# auto_shield_final.net
KiCad netlist of a schematic drawn in EAGLE
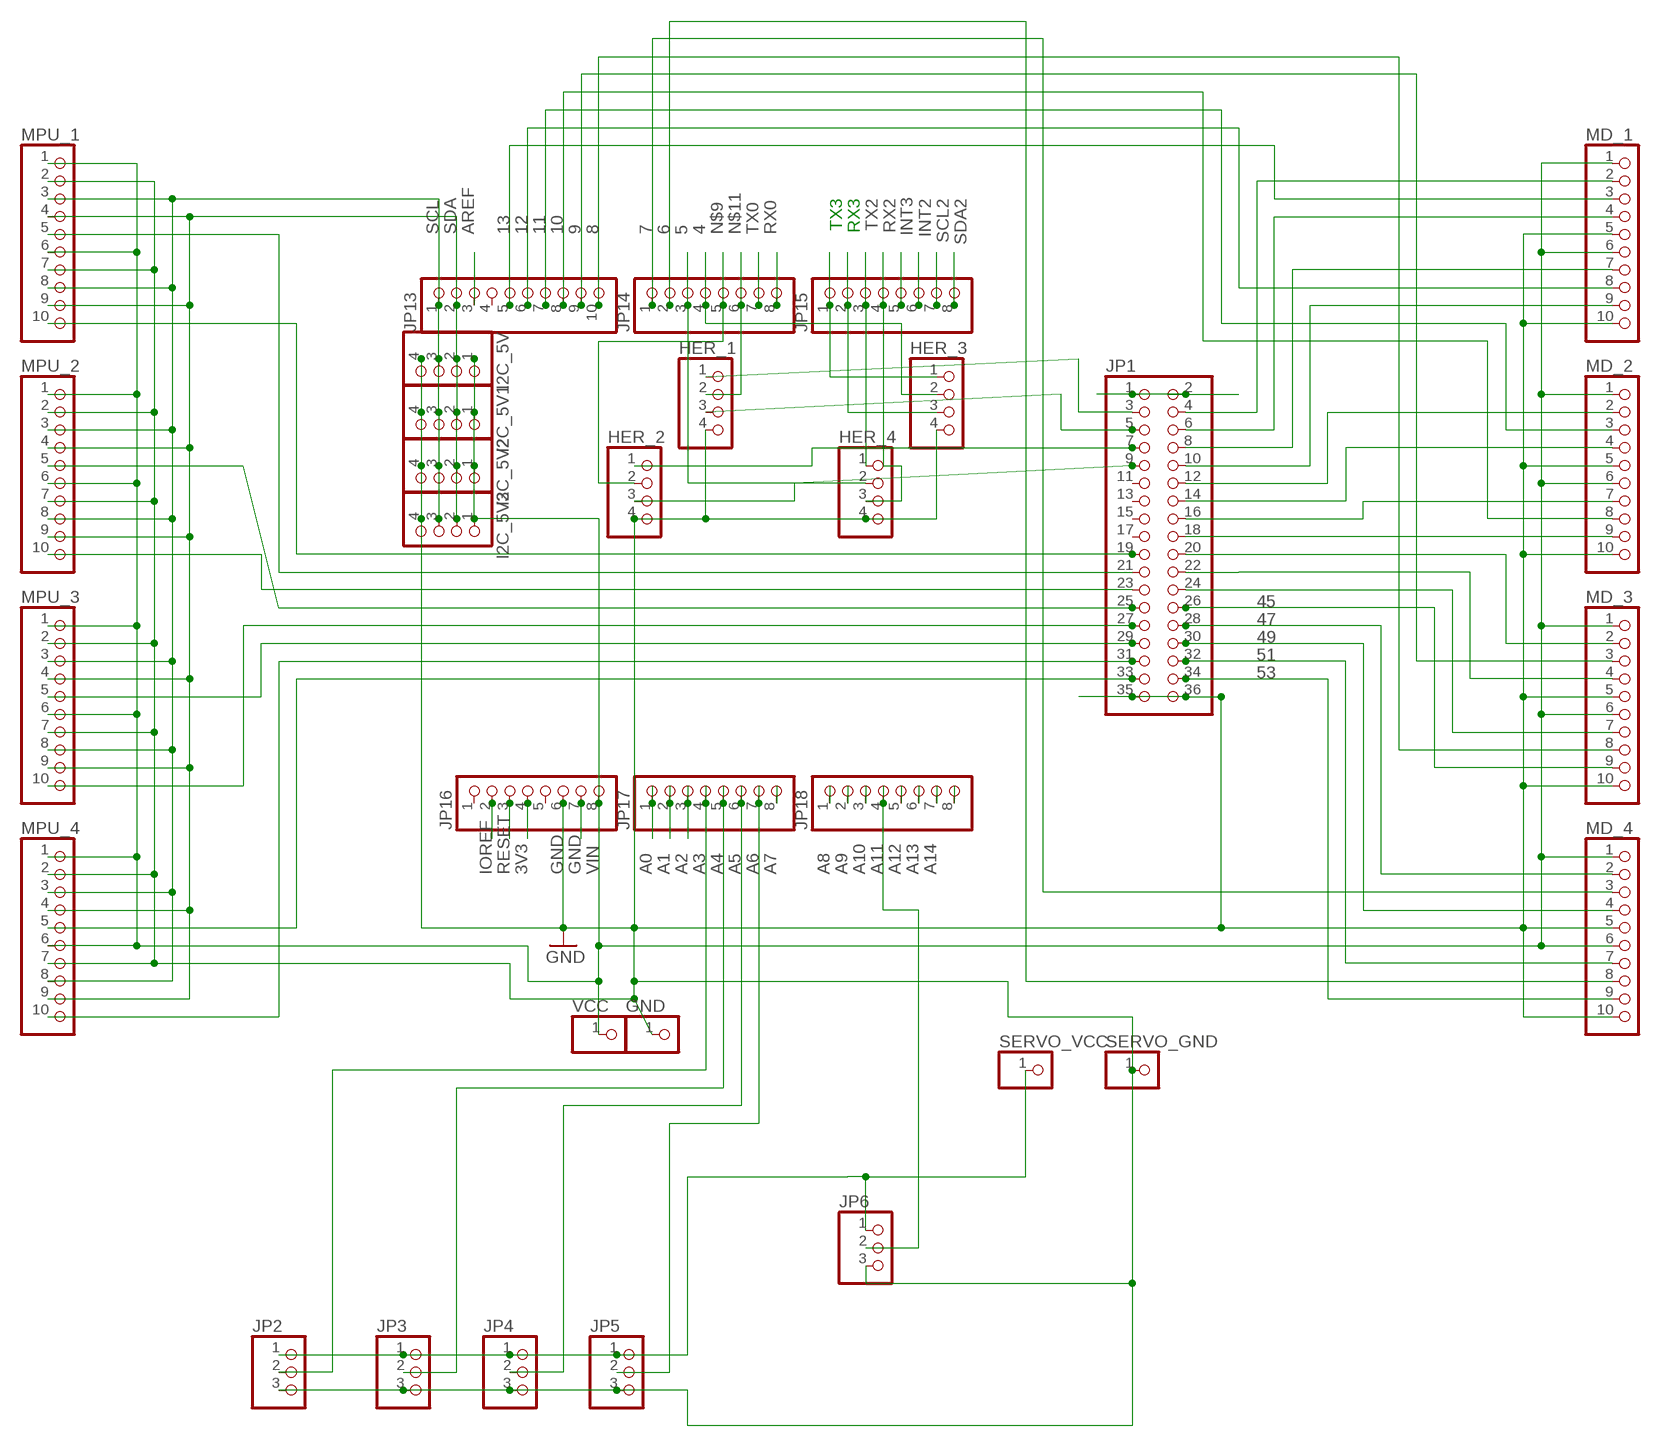
[diagram p0: schematic, sheet 1]

(export (version "E")
  (design (tool "Eeschema 10.0.6"))
  (components
    (comp (ref "GND")
      (value "PINHD-1X1")
      (footprint "eagle-import:1X01")
      (libsource (lib "eagle-import") (part "PINHD-1X1"))
    )
    (comp (ref "HER_1")
      (value "PINHD-1X4")
      (footprint "eagle-import:1X04")
      (libsource (lib "eagle-import") (part "PINHD-1X4"))
    )
    (comp (ref "HER_2")
      (value "PINHD-1X4")
      (footprint "eagle-import:1X04")
      (libsource (lib "eagle-import") (part "PINHD-1X4"))
    )
    (comp (ref "HER_3")
      (value "PINHD-1X4")
      (footprint "eagle-import:1X04")
      (libsource (lib "eagle-import") (part "PINHD-1X4"))
    )
    (comp (ref "HER_4")
      (value "PINHD-1X4")
      (footprint "eagle-import:1X04")
      (libsource (lib "eagle-import") (part "PINHD-1X4"))
    )
    (comp (ref "I2C_5V")
      (value "PINHD-1X4")
      (footprint "eagle-import:1X04")
      (libsource (lib "eagle-import") (part "PINHD-1X4"))
    )
    (comp (ref "I2C_5V1")
      (value "PINHD-1X4")
      (footprint "eagle-import:1X04")
      (libsource (lib "eagle-import") (part "PINHD-1X4"))
    )
    (comp (ref "I2C_5V2")
      (value "PINHD-1X4")
      (footprint "eagle-import:1X04")
      (libsource (lib "eagle-import") (part "PINHD-1X4"))
    )
    (comp (ref "I2C_5V3")
      (value "PINHD-1X4")
      (footprint "eagle-import:1X04")
      (libsource (lib "eagle-import") (part "PINHD-1X4"))
    )
    (comp (ref "JP1")
      (value "PINHD-2X18")
      (footprint "eagle-import:2X18")
      (libsource (lib "eagle-import") (part "PINHD-2X18"))
    )
    (comp (ref "JP2")
      (value "PINHD-1X3")
      (footprint "eagle-import:1X03")
      (libsource (lib "eagle-import") (part "PINHD-1X3"))
    )
    (comp (ref "JP3")
      (value "PINHD-1X3")
      (footprint "eagle-import:1X03")
      (libsource (lib "eagle-import") (part "PINHD-1X3"))
    )
    (comp (ref "JP4")
      (value "PINHD-1X3")
      (footprint "eagle-import:1X03")
      (libsource (lib "eagle-import") (part "PINHD-1X3"))
    )
    (comp (ref "JP5")
      (value "PINHD-1X3")
      (footprint "eagle-import:1X03")
      (libsource (lib "eagle-import") (part "PINHD-1X3"))
    )
    (comp (ref "JP6")
      (value "PINHD-1X3")
      (footprint "eagle-import:1X03")
      (libsource (lib "eagle-import") (part "PINHD-1X3"))
    )
    (comp (ref "JP13")
      (value "PINHD-1X10")
      (footprint "eagle-import:1X10")
      (libsource (lib "eagle-import") (part "PINHD-1X10"))
    )
    (comp (ref "JP14")
      (value "PINHD-1X8")
      (footprint "eagle-import:1X08")
      (libsource (lib "eagle-import") (part "PINHD-1X8"))
    )
    (comp (ref "JP15")
      (value "PINHD-1X8")
      (footprint "eagle-import:1X08")
      (libsource (lib "eagle-import") (part "PINHD-1X8"))
    )
    (comp (ref "JP16")
      (value "PINHD-1X8")
      (footprint "eagle-import:1X08")
      (libsource (lib "eagle-import") (part "PINHD-1X8"))
    )
    (comp (ref "JP17")
      (value "PINHD-1X8")
      (footprint "eagle-import:1X08")
      (libsource (lib "eagle-import") (part "PINHD-1X8"))
    )
    (comp (ref "JP18")
      (value "PINHD-1X8")
      (footprint "eagle-import:1X08")
      (libsource (lib "eagle-import") (part "PINHD-1X8"))
    )
    (comp (ref "MD_1")
      (value "PINHD-1X10")
      (footprint "eagle-import:1X10")
      (libsource (lib "eagle-import") (part "pinhead_325_PINHD-1X10"))
    )
    (comp (ref "MD_2")
      (value "PINHD-1X10")
      (footprint "eagle-import:1X10")
      (libsource (lib "eagle-import") (part "pinhead_325_PINHD-1X10"))
    )
    (comp (ref "MD_3")
      (value "PINHD-1X10")
      (footprint "eagle-import:1X10")
      (libsource (lib "eagle-import") (part "pinhead_325_PINHD-1X10"))
    )
    (comp (ref "MD_4")
      (value "PINHD-1X10")
      (footprint "eagle-import:1X10")
      (libsource (lib "eagle-import") (part "pinhead_325_PINHD-1X10"))
    )
    (comp (ref "MPU_1")
      (value "PINHD-1X10")
      (footprint "eagle-import:1X10")
      (libsource (lib "eagle-import") (part "pinhead_325_PINHD-1X10"))
    )
    (comp (ref "MPU_2")
      (value "PINHD-1X10")
      (footprint "eagle-import:1X10")
      (libsource (lib "eagle-import") (part "pinhead_325_PINHD-1X10"))
    )
    (comp (ref "MPU_3")
      (value "PINHD-1X10")
      (footprint "eagle-import:1X10")
      (libsource (lib "eagle-import") (part "pinhead_325_PINHD-1X10"))
    )
    (comp (ref "MPU_4")
      (value "PINHD-1X10")
      (footprint "eagle-import:1X10")
      (libsource (lib "eagle-import") (part "pinhead_325_PINHD-1X10"))
    )
    (comp (ref "SERVO_GND")
      (value "PINHD-1X1")
      (footprint "eagle-import:1X01")
      (libsource (lib "eagle-import") (part "PINHD-1X1"))
    )
    (comp (ref "SERVO_VCC")
      (value "PINHD-1X1")
      (footprint "eagle-import:1X01")
      (libsource (lib "eagle-import") (part "PINHD-1X1"))
    )
    (comp (ref "VCC")
      (value "PINHD-1X1")
      (footprint "eagle-import:1X01")
      (libsource (lib "eagle-import") (part "PINHD-1X1"))
    )
  )
  (nets
    (net (code "1") (name "/3V3") (class "Default")
      (node (ref "JP16") (pin "4") (pinfunction "4_4") (pintype "passive"))
    )
    (net (code "2") (name "/4") (class "Default")
      (node (ref "HER_3") (pin "2") (pinfunction "2_2") (pintype "passive"))
      (node (ref "JP14") (pin "4") (pinfunction "4_4") (pintype "passive"))
    )
    (net (code "3") (name "/5") (class "Default")
      (node (ref "HER_4") (pin "2") (pinfunction "2_2") (pintype "passive"))
      (node (ref "JP14") (pin "3") (pinfunction "3_3") (pintype "passive"))
    )
    (net (code "4") (name "/6") (class "Default")
      (node (ref "JP14") (pin "2") (pinfunction "2_2") (pintype "passive"))
      (node (ref "MD_4") (pin "8") (pinfunction "8_8") (pintype "passive"))
    )
    (net (code "5") (name "/7") (class "Default")
      (node (ref "JP14") (pin "1") (pinfunction "1_1") (pintype "passive"))
      (node (ref "MD_4") (pin "3") (pinfunction "3_3") (pintype "passive"))
    )
    (net (code "6") (name "/8") (class "Default")
      (node (ref "JP13") (pin "10") (pinfunction "10_10") (pintype "passive"))
      (node (ref "MD_3") (pin "8") (pinfunction "8_8") (pintype "passive"))
    )
    (net (code "7") (name "/9") (class "Default")
      (node (ref "JP13") (pin "9") (pinfunction "9_9") (pintype "passive"))
      (node (ref "MD_3") (pin "3") (pinfunction "3_3") (pintype "passive"))
    )
    (net (code "8") (name "/10") (class "Default")
      (node (ref "JP13") (pin "8") (pinfunction "8_8") (pintype "passive"))
      (node (ref "MD_2") (pin "8") (pinfunction "8_8") (pintype "passive"))
    )
    (net (code "9") (name "/11") (class "Default")
      (node (ref "JP13") (pin "7") (pinfunction "7_7") (pintype "passive"))
      (node (ref "MD_2") (pin "3") (pinfunction "3_3") (pintype "passive"))
    )
    (net (code "10") (name "/12") (class "Default")
      (node (ref "JP13") (pin "6") (pinfunction "6_6") (pintype "passive"))
      (node (ref "MD_1") (pin "8") (pinfunction "8_8") (pintype "passive"))
    )
    (net (code "11") (name "/13") (class "Default")
      (node (ref "JP13") (pin "5") (pinfunction "5_5") (pintype "passive"))
      (node (ref "MD_1") (pin "3") (pinfunction "3_3") (pintype "passive"))
    )
    (net (code "12") (name "/45") (class "Default")
      (node (ref "JP1") (pin "26") (pinfunction "26_26") (pintype "passive"))
      (node (ref "MD_3") (pin "9") (pinfunction "9_9") (pintype "passive"))
    )
    (net (code "13") (name "/47") (class "Default")
      (node (ref "JP1") (pin "28") (pinfunction "28_28") (pintype "passive"))
      (node (ref "MD_4") (pin "2") (pinfunction "2_2") (pintype "passive"))
    )
    (net (code "14") (name "/49") (class "Default")
      (node (ref "JP1") (pin "30") (pinfunction "30_30") (pintype "passive"))
      (node (ref "MD_4") (pin "4") (pinfunction "4_4") (pintype "passive"))
    )
    (net (code "15") (name "/51") (class "Default")
      (node (ref "JP1") (pin "32") (pinfunction "32_32") (pintype "passive"))
      (node (ref "MD_4") (pin "7") (pinfunction "7_7") (pintype "passive"))
    )
    (net (code "16") (name "/53") (class "Default")
      (node (ref "JP1") (pin "34") (pinfunction "34_34") (pintype "passive"))
      (node (ref "MD_4") (pin "9") (pinfunction "9_9") (pintype "passive"))
    )
    (net (code "17") (name "/A0") (class "Default")
      (node (ref "JP17") (pin "1") (pinfunction "1_1") (pintype "passive"))
    )
    (net (code "18") (name "/A1") (class "Default")
      (node (ref "JP17") (pin "2") (pinfunction "2_2") (pintype "passive"))
    )
    (net (code "19") (name "/A2") (class "Default")
      (node (ref "JP17") (pin "3") (pinfunction "3_3") (pintype "passive"))
    )
    (net (code "20") (name "/A3") (class "Default")
      (node (ref "JP17") (pin "4") (pinfunction "4_4") (pintype "passive"))
      (node (ref "JP2") (pin "2") (pinfunction "2_2") (pintype "passive"))
    )
    (net (code "21") (name "/A4") (class "Default")
      (node (ref "JP17") (pin "5") (pinfunction "5_5") (pintype "passive"))
      (node (ref "JP3") (pin "2") (pinfunction "2_2") (pintype "passive"))
    )
    (net (code "22") (name "/A5") (class "Default")
      (node (ref "JP17") (pin "6") (pinfunction "6_6") (pintype "passive"))
      (node (ref "JP4") (pin "2") (pinfunction "2_2") (pintype "passive"))
    )
    (net (code "23") (name "/A6") (class "Default")
      (node (ref "JP17") (pin "7") (pinfunction "7_7") (pintype "passive"))
      (node (ref "JP5") (pin "2") (pinfunction "2_2") (pintype "passive"))
    )
    (net (code "24") (name "/A7") (class "Default")
      (node (ref "JP17") (pin "8") (pinfunction "8_8") (pintype "passive"))
    )
    (net (code "25") (name "/A8") (class "Default")
      (node (ref "JP18") (pin "1") (pinfunction "1_1") (pintype "passive"))
    )
    (net (code "26") (name "/A9") (class "Default")
      (node (ref "JP18") (pin "2") (pinfunction "2_2") (pintype "passive"))
    )
    (net (code "27") (name "/A10") (class "Default")
      (node (ref "JP18") (pin "3") (pinfunction "3_3") (pintype "passive"))
    )
    (net (code "28") (name "/A11") (class "Default")
      (node (ref "JP18") (pin "4") (pinfunction "4_4") (pintype "passive"))
      (node (ref "JP6") (pin "2") (pinfunction "2_2") (pintype "passive"))
    )
    (net (code "29") (name "/A12") (class "Default")
      (node (ref "JP18") (pin "5") (pinfunction "5_5") (pintype "passive"))
    )
    (net (code "30") (name "/A13") (class "Default")
      (node (ref "JP18") (pin "6") (pinfunction "6_6") (pintype "passive"))
    )
    (net (code "31") (name "/A14") (class "Default")
      (node (ref "JP18") (pin "7") (pinfunction "7_7") (pintype "passive"))
    )
    (net (code "32") (name "/AREF") (class "Default")
      (node (ref "JP13") (pin "3") (pinfunction "3_3") (pintype "passive"))
    )
    (net (code "33") (name "/INT2") (class "Default")
      (node (ref "JP15") (pin "6") (pinfunction "6_6") (pintype "passive"))
    )
    (net (code "34") (name "/INT3") (class "Default")
      (node (ref "JP15") (pin "5") (pinfunction "5_5") (pintype "passive"))
    )
    (net (code "35") (name "/IOREF") (class "Default")
      (node (ref "JP16") (pin "2") (pinfunction "2_2") (pintype "passive"))
    )
    (net (code "36") (name "/N$9") (class "Default")
      (node (ref "HER_2") (pin "2") (pinfunction "2_2") (pintype "passive"))
      (node (ref "JP14") (pin "5") (pinfunction "5_5") (pintype "passive"))
    )
    (net (code "37") (name "/N$11") (class "Default")
      (node (ref "HER_1") (pin "2") (pinfunction "2_2") (pintype "passive"))
      (node (ref "JP14") (pin "6") (pinfunction "6_6") (pintype "passive"))
    )
    (net (code "38") (name "/RESET") (class "Default")
      (node (ref "JP16") (pin "3") (pinfunction "3_3") (pintype "passive"))
    )
    (net (code "39") (name "/RX0") (class "Default")
      (node (ref "JP14") (pin "8") (pinfunction "8_8") (pintype "passive"))
    )
    (net (code "40") (name "/RX2") (class "Default")
      (node (ref "HER_4") (pin "3") (pinfunction "3_3") (pintype "passive"))
      (node (ref "JP15") (pin "4") (pinfunction "4_4") (pintype "passive"))
    )
    (net (code "41") (name "/RX3") (class "Default")
      (node (ref "HER_3") (pin "3") (pinfunction "3_3") (pintype "passive"))
      (node (ref "JP15") (pin "2") (pinfunction "2_2") (pintype "passive"))
    )
    (net (code "42") (name "/SCL") (class "Default")
      (node (ref "I2C_5V") (pin "3") (pinfunction "3_3") (pintype "passive"))
      (node (ref "I2C_5V1") (pin "3") (pinfunction "3_3") (pintype "passive"))
      (node (ref "I2C_5V2") (pin "3") (pinfunction "3_3") (pintype "passive"))
      (node (ref "I2C_5V3") (pin "3") (pinfunction "3_3") (pintype "passive"))
      (node (ref "JP13") (pin "1") (pinfunction "1_1") (pintype "passive"))
      (node (ref "MPU_1") (pin "3") (pinfunction "3_3") (pintype "passive"))
      (node (ref "MPU_1") (pin "8") (pinfunction "8_8") (pintype "passive"))
      (node (ref "MPU_2") (pin "3") (pinfunction "3_3") (pintype "passive"))
      (node (ref "MPU_2") (pin "8") (pinfunction "8_8") (pintype "passive"))
      (node (ref "MPU_3") (pin "3") (pinfunction "3_3") (pintype "passive"))
      (node (ref "MPU_3") (pin "8") (pinfunction "8_8") (pintype "passive"))
      (node (ref "MPU_4") (pin "3") (pinfunction "3_3") (pintype "passive"))
      (node (ref "MPU_4") (pin "8") (pinfunction "8_8") (pintype "passive"))
    )
    (net (code "43") (name "/SCL2") (class "Default")
      (node (ref "JP15") (pin "7") (pinfunction "7_7") (pintype "passive"))
    )
    (net (code "44") (name "/SDA") (class "Default")
      (node (ref "I2C_5V") (pin "2") (pinfunction "2_2") (pintype "passive"))
      (node (ref "I2C_5V1") (pin "2") (pinfunction "2_2") (pintype "passive"))
      (node (ref "I2C_5V2") (pin "2") (pinfunction "2_2") (pintype "passive"))
      (node (ref "I2C_5V3") (pin "2") (pinfunction "2_2") (pintype "passive"))
      (node (ref "JP13") (pin "2") (pinfunction "2_2") (pintype "passive"))
      (node (ref "MPU_1") (pin "4") (pinfunction "4_4") (pintype "passive"))
      (node (ref "MPU_1") (pin "9") (pinfunction "9_9") (pintype "passive"))
      (node (ref "MPU_2") (pin "4") (pinfunction "4_4") (pintype "passive"))
      (node (ref "MPU_2") (pin "9") (pinfunction "9_9") (pintype "passive"))
      (node (ref "MPU_3") (pin "4") (pinfunction "4_4") (pintype "passive"))
      (node (ref "MPU_3") (pin "9") (pinfunction "9_9") (pintype "passive"))
      (node (ref "MPU_4") (pin "4") (pinfunction "4_4") (pintype "passive"))
      (node (ref "MPU_4") (pin "9") (pinfunction "9_9") (pintype "passive"))
    )
    (net (code "45") (name "/SDA2") (class "Default")
      (node (ref "JP15") (pin "8") (pinfunction "8_8") (pintype "passive"))
    )
    (net (code "46") (name "/TX0") (class "Default")
      (node (ref "JP14") (pin "7") (pinfunction "7_7") (pintype "passive"))
    )
    (net (code "47") (name "/TX2") (class "Default")
      (node (ref "HER_4") (pin "1") (pinfunction "1_1") (pintype "passive"))
      (node (ref "JP15") (pin "3") (pinfunction "3_3") (pintype "passive"))
    )
    (net (code "48") (name "/TX3") (class "Default")
      (node (ref "HER_3") (pin "1") (pinfunction "1_1") (pintype "passive"))
      (node (ref "JP15") (pin "1") (pinfunction "1_1") (pintype "passive"))
    )
    (net (code "49") (name "/VIN") (class "Default")
      (node (ref "I2C_5V") (pin "1") (pinfunction "1_1") (pintype "passive"))
      (node (ref "I2C_5V1") (pin "1") (pinfunction "1_1") (pintype "passive"))
      (node (ref "I2C_5V2") (pin "1") (pinfunction "1_1") (pintype "passive"))
      (node (ref "I2C_5V3") (pin "1") (pinfunction "1_1") (pintype "passive"))
      (node (ref "JP16") (pin "8") (pinfunction "8_8") (pintype "passive"))
      (node (ref "MD_1") (pin "1") (pinfunction "1_1") (pintype "passive"))
      (node (ref "MD_1") (pin "6") (pinfunction "6_6") (pintype "passive"))
      (node (ref "MD_2") (pin "1") (pinfunction "1_1") (pintype "passive"))
      (node (ref "MD_2") (pin "6") (pinfunction "6_6") (pintype "passive"))
      (node (ref "MD_3") (pin "1") (pinfunction "1_1") (pintype "passive"))
      (node (ref "MD_3") (pin "6") (pinfunction "6_6") (pintype "passive"))
      (node (ref "MD_4") (pin "1") (pinfunction "1_1") (pintype "passive"))
      (node (ref "MD_4") (pin "6") (pinfunction "6_6") (pintype "passive"))
      (node (ref "MPU_1") (pin "1") (pinfunction "1_1") (pintype "passive"))
      (node (ref "MPU_1") (pin "6") (pinfunction "6_6") (pintype "passive"))
      (node (ref "MPU_2") (pin "1") (pinfunction "1_1") (pintype "passive"))
      (node (ref "MPU_2") (pin "6") (pinfunction "6_6") (pintype "passive"))
      (node (ref "MPU_3") (pin "1") (pinfunction "1_1") (pintype "passive"))
      (node (ref "MPU_3") (pin "6") (pinfunction "6_6") (pintype "passive"))
      (node (ref "MPU_4") (pin "1") (pinfunction "1_1") (pintype "passive"))
      (node (ref "MPU_4") (pin "6") (pinfunction "6_6") (pintype "passive"))
      (node (ref "VCC") (pin "1") (pinfunction "1_1") (pintype "passive"))
    )
    (net (code "50") (name "GND") (class "Default")
      (node (ref "GND") (pin "1") (pinfunction "1_1") (pintype "passive"))
      (node (ref "HER_1") (pin "4") (pinfunction "4_4") (pintype "passive"))
      (node (ref "HER_2") (pin "4") (pinfunction "4_4") (pintype "passive"))
      (node (ref "HER_3") (pin "4") (pinfunction "4_4") (pintype "passive"))
      (node (ref "HER_4") (pin "4") (pinfunction "4_4") (pintype "passive"))
      (node (ref "I2C_5V") (pin "4") (pinfunction "4_4") (pintype "passive"))
      (node (ref "I2C_5V1") (pin "4") (pinfunction "4_4") (pintype "passive"))
      (node (ref "I2C_5V2") (pin "4") (pinfunction "4_4") (pintype "passive"))
      (node (ref "I2C_5V3") (pin "4") (pinfunction "4_4") (pintype "passive"))
      (node (ref "JP1") (pin "35") (pinfunction "35_35") (pintype "passive"))
      (node (ref "JP1") (pin "36") (pinfunction "36_36") (pintype "passive"))
      (node (ref "JP16") (pin "6") (pinfunction "6_6") (pintype "passive"))
      (node (ref "JP16") (pin "7") (pinfunction "7_7") (pintype "passive"))
      (node (ref "JP2") (pin "3") (pinfunction "3_3") (pintype "passive"))
      (node (ref "JP3") (pin "3") (pinfunction "3_3") (pintype "passive"))
      (node (ref "JP4") (pin "3") (pinfunction "3_3") (pintype "passive"))
      (node (ref "JP5") (pin "3") (pinfunction "3_3") (pintype "passive"))
      (node (ref "JP6") (pin "3") (pinfunction "3_3") (pintype "passive"))
      (node (ref "MD_1") (pin "10") (pinfunction "10_10") (pintype "passive"))
      (node (ref "MD_1") (pin "5") (pinfunction "5_5") (pintype "passive"))
      (node (ref "MD_2") (pin "10") (pinfunction "10_10") (pintype "passive"))
      (node (ref "MD_2") (pin "5") (pinfunction "5_5") (pintype "passive"))
      (node (ref "MD_3") (pin "10") (pinfunction "10_10") (pintype "passive"))
      (node (ref "MD_3") (pin "5") (pinfunction "5_5") (pintype "passive"))
      (node (ref "MD_4") (pin "10") (pinfunction "10_10") (pintype "passive"))
      (node (ref "MD_4") (pin "5") (pinfunction "5_5") (pintype "passive"))
      (node (ref "MPU_1") (pin "2") (pinfunction "2_2") (pintype "passive"))
      (node (ref "MPU_1") (pin "7") (pinfunction "7_7") (pintype "passive"))
      (node (ref "MPU_2") (pin "2") (pinfunction "2_2") (pintype "passive"))
      (node (ref "MPU_2") (pin "7") (pinfunction "7_7") (pintype "passive"))
      (node (ref "MPU_3") (pin "2") (pinfunction "2_2") (pintype "passive"))
      (node (ref "MPU_3") (pin "7") (pinfunction "7_7") (pintype "passive"))
      (node (ref "MPU_4") (pin "2") (pinfunction "2_2") (pintype "passive"))
      (node (ref "MPU_4") (pin "7") (pinfunction "7_7") (pintype "passive"))
      (node (ref "SERVO_GND") (pin "1") (pinfunction "1_1") (pintype "passive"))
    )
    (net (code "51") (name "Net-(HER_1-Pad1)") (class "Default")
      (node (ref "HER_1") (pin "1") (pinfunction "1_1") (pintype "passive"))
      (node (ref "JP1") (pin "3") (pinfunction "3_3") (pintype "passive"))
    )
    (net (code "52") (name "Net-(HER_1-Pad3)") (class "Default")
      (node (ref "HER_1") (pin "3") (pinfunction "3_3") (pintype "passive"))
      (node (ref "JP1") (pin "5") (pinfunction "5_5") (pintype "passive"))
    )
    (net (code "53") (name "Net-(HER_2-Pad1)") (class "Default")
      (node (ref "HER_2") (pin "1") (pinfunction "1_1") (pintype "passive"))
      (node (ref "JP1") (pin "7") (pinfunction "7_7") (pintype "passive"))
    )
    (net (code "54") (name "Net-(HER_2-Pad3)") (class "Default")
      (node (ref "HER_2") (pin "3") (pinfunction "3_3") (pintype "passive"))
      (node (ref "JP1") (pin "9") (pinfunction "9_9") (pintype "passive"))
    )
    (net (code "55") (name "Net-(JP1-Pad1)") (class "Default")
      (node (ref "JP1") (pin "1") (pinfunction "1_1") (pintype "passive"))
      (node (ref "JP1") (pin "2") (pinfunction "2_2") (pintype "passive"))
    )
    (net (code "56") (name "Net-(JP1-Pad4)") (class "Default")
      (node (ref "JP1") (pin "4") (pinfunction "4_4") (pintype "passive"))
      (node (ref "MD_1") (pin "2") (pinfunction "2_2") (pintype "passive"))
    )
    (net (code "57") (name "Net-(JP1-Pad6)") (class "Default")
      (node (ref "JP1") (pin "6") (pinfunction "6_6") (pintype "passive"))
      (node (ref "MD_1") (pin "4") (pinfunction "4_4") (pintype "passive"))
    )
    (net (code "58") (name "Net-(JP1-Pad8)") (class "Default")
      (node (ref "JP1") (pin "8") (pinfunction "8_8") (pintype "passive"))
      (node (ref "MD_1") (pin "7") (pinfunction "7_7") (pintype "passive"))
    )
    (net (code "59") (name "Net-(JP1-Pad10)") (class "Default")
      (node (ref "JP1") (pin "10") (pinfunction "10_10") (pintype "passive"))
      (node (ref "MD_1") (pin "9") (pinfunction "9_9") (pintype "passive"))
    )
    (net (code "60") (name "Net-(JP1-Pad12)") (class "Default")
      (node (ref "JP1") (pin "12") (pinfunction "12_12") (pintype "passive"))
      (node (ref "MD_2") (pin "2") (pinfunction "2_2") (pintype "passive"))
    )
    (net (code "61") (name "Net-(JP1-Pad14)") (class "Default")
      (node (ref "JP1") (pin "14") (pinfunction "14_14") (pintype "passive"))
      (node (ref "MD_2") (pin "4") (pinfunction "4_4") (pintype "passive"))
    )
    (net (code "62") (name "Net-(JP1-Pad16)") (class "Default")
      (node (ref "JP1") (pin "16") (pinfunction "16_16") (pintype "passive"))
      (node (ref "MD_2") (pin "7") (pinfunction "7_7") (pintype "passive"))
    )
    (net (code "63") (name "Net-(JP1-Pad18)") (class "Default")
      (node (ref "JP1") (pin "18") (pinfunction "18_18") (pintype "passive"))
      (node (ref "MD_2") (pin "9") (pinfunction "9_9") (pintype "passive"))
    )
    (net (code "64") (name "Net-(JP1-Pad19)") (class "Default")
      (node (ref "JP1") (pin "19") (pinfunction "19_19") (pintype "passive"))
      (node (ref "MPU_1") (pin "10") (pinfunction "10_10") (pintype "passive"))
    )
    (net (code "65") (name "Net-(JP1-Pad20)") (class "Default")
      (node (ref "JP1") (pin "20") (pinfunction "20_20") (pintype "passive"))
      (node (ref "MD_3") (pin "2") (pinfunction "2_2") (pintype "passive"))
    )
    (net (code "66") (name "Net-(JP1-Pad21)") (class "Default")
      (node (ref "JP1") (pin "21") (pinfunction "21_21") (pintype "passive"))
      (node (ref "MPU_1") (pin "5") (pinfunction "5_5") (pintype "passive"))
    )
    (net (code "67") (name "Net-(JP1-Pad22)") (class "Default")
      (node (ref "JP1") (pin "22") (pinfunction "22_22") (pintype "passive"))
      (node (ref "MD_3") (pin "4") (pinfunction "4_4") (pintype "passive"))
    )
    (net (code "68") (name "Net-(JP1-Pad23)") (class "Default")
      (node (ref "JP1") (pin "23") (pinfunction "23_23") (pintype "passive"))
      (node (ref "MPU_2") (pin "10") (pinfunction "10_10") (pintype "passive"))
    )
    (net (code "69") (name "Net-(JP1-Pad24)") (class "Default")
      (node (ref "JP1") (pin "24") (pinfunction "24_24") (pintype "passive"))
      (node (ref "MD_3") (pin "7") (pinfunction "7_7") (pintype "passive"))
    )
    (net (code "70") (name "Net-(JP1-Pad25)") (class "Default")
      (node (ref "JP1") (pin "25") (pinfunction "25_25") (pintype "passive"))
      (node (ref "MPU_2") (pin "5") (pinfunction "5_5") (pintype "passive"))
    )
    (net (code "71") (name "Net-(JP1-Pad27)") (class "Default")
      (node (ref "JP1") (pin "27") (pinfunction "27_27") (pintype "passive"))
      (node (ref "MPU_3") (pin "10") (pinfunction "10_10") (pintype "passive"))
    )
    (net (code "72") (name "Net-(JP1-Pad29)") (class "Default")
      (node (ref "JP1") (pin "29") (pinfunction "29_29") (pintype "passive"))
      (node (ref "MPU_3") (pin "5") (pinfunction "5_5") (pintype "passive"))
    )
    (net (code "73") (name "Net-(JP1-Pad31)") (class "Default")
      (node (ref "JP1") (pin "31") (pinfunction "31_31") (pintype "passive"))
      (node (ref "MPU_4") (pin "10") (pinfunction "10_10") (pintype "passive"))
    )
    (net (code "74") (name "Net-(JP1-Pad33)") (class "Default")
      (node (ref "JP1") (pin "33") (pinfunction "33_33") (pintype "passive"))
      (node (ref "MPU_4") (pin "5") (pinfunction "5_5") (pintype "passive"))
    )
    (net (code "75") (name "Net-(JP2-Pad1)") (class "Default")
      (node (ref "JP2") (pin "1") (pinfunction "1_1") (pintype "passive"))
      (node (ref "JP3") (pin "1") (pinfunction "1_1") (pintype "passive"))
      (node (ref "JP4") (pin "1") (pinfunction "1_1") (pintype "passive"))
      (node (ref "JP5") (pin "1") (pinfunction "1_1") (pintype "passive"))
      (node (ref "JP6") (pin "1") (pinfunction "1_1") (pintype "passive"))
      (node (ref "SERVO_VCC") (pin "1") (pinfunction "1_1") (pintype "passive"))
    )
    (net (code "76") (name "unconnected-(JP1-Pad11)") (class "Default")
      (node (ref "JP1") (pin "11") (pinfunction "11_11") (pintype "passive"))
    )
    (net (code "77") (name "unconnected-(JP1-Pad13)") (class "Default")
      (node (ref "JP1") (pin "13") (pinfunction "13_13") (pintype "passive"))
    )
    (net (code "78") (name "unconnected-(JP1-Pad15)") (class "Default")
      (node (ref "JP1") (pin "15") (pinfunction "15_15") (pintype "passive"))
    )
    (net (code "79") (name "unconnected-(JP1-Pad17)") (class "Default")
      (node (ref "JP1") (pin "17") (pinfunction "17_17") (pintype "passive"))
    )
    (net (code "80") (name "unconnected-(JP13-Pad4)") (class "Default")
      (node (ref "JP13") (pin "4") (pinfunction "4_4") (pintype "passive"))
    )
    (net (code "81") (name "unconnected-(JP16-Pad1)") (class "Default")
      (node (ref "JP16") (pin "1") (pinfunction "1_1") (pintype "passive"))
    )
    (net (code "82") (name "unconnected-(JP16-Pad5)") (class "Default")
      (node (ref "JP16") (pin "5") (pinfunction "5_5") (pintype "passive"))
    )
    (net (code "83") (name "unconnected-(JP18-Pad8)") (class "Default")
      (node (ref "JP18") (pin "8") (pinfunction "8_8") (pintype "passive"))
    )
  )
)
